# ECB01-Kit-V1_0.net
KiCad netlist of a schematic drawn in Altium Designer
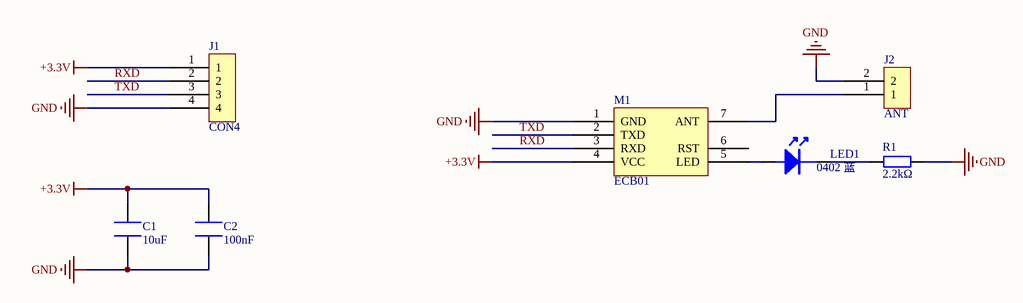
[diagram p0: ECB01-Kit-V1.0.SchDoc]

(export (version "E")
  (design (tool "Eeschema 10.0.6"))
  (components
    (comp (ref "C1") (value "10uF") (footprint "0402") (libsource (lib "ECB01-Kit-V1.0") (part "C")))
    (comp (ref "C2") (value "100nF") (footprint "0402") (libsource (lib "ECB01-Kit-V1.0") (part "C")))
    (comp (ref "J1") (value "CON4") (footprint "SIP04") (libsource (lib "ECB01-Kit-V1.0") (part "CON4")))
    (comp (ref "J2") (value "ANT") (footprint "SMA") (libsource (lib "ECB01-Kit-V1.0") (part "ANT")))
    (comp (ref "LED1")
      (value "0402 蓝")
      (footprint "0402-led")
      (libsource (lib "ECB01-Kit-V1.0") (part "LED-0402"))
    )
    (comp (ref "M1") (value "ECB01") (footprint "ECB01") (libsource (lib "ECB01-Kit-V1.0") (part "ECB01")))
    (comp (ref "R1") (value "2.2kΩ") (footprint "0402") (libsource (lib "ECB01-Kit-V1.0") (part "R")))
  )
  (nets
    (net (code "1") (name "+3.3V") (class "Default")
      (node (ref "C1") (pin "2") (pinfunction "2_2") (pintype "passive"))
      (node (ref "C2") (pin "2") (pinfunction "2_2") (pintype "passive"))
      (node (ref "J1") (pin "1") (pinfunction "1_1") (pintype "passive"))
      (node (ref "M1") (pin "4") (pinfunction "VCC_4") (pintype "passive"))
    )
    (net (code "2") (name "/RXD") (class "Default")
      (node (ref "J1") (pin "2") (pinfunction "2_2") (pintype "passive"))
      (node (ref "M1") (pin "3") (pinfunction "RXD_3") (pintype "passive"))
    )
    (net (code "3") (name "/TXD") (class "Default")
      (node (ref "J1") (pin "3") (pinfunction "3_3") (pintype "passive"))
      (node (ref "M1") (pin "2") (pinfunction "TXD_2") (pintype "passive"))
    )
    (net (code "4") (name "GND") (class "Default")
      (node (ref "C1") (pin "1") (pinfunction "1_1") (pintype "passive"))
      (node (ref "C2") (pin "1") (pinfunction "1_1") (pintype "passive"))
      (node (ref "J1") (pin "4") (pinfunction "4_4") (pintype "passive"))
      (node (ref "J2") (pin "2") (pinfunction "2_2") (pintype "passive"))
      (node (ref "M1") (pin "1") (pinfunction "GND_1") (pintype "passive"))
      (node (ref "R1") (pin "2") (pinfunction "2_2") (pintype "passive"))
    )
    (net (code "5") (name "Net-(LED1-Pad2)") (class "Default")
      (node (ref "LED1") (pin "2") (pinfunction "2_2") (pintype "passive"))
      (node (ref "R1") (pin "1") (pinfunction "1_1") (pintype "passive"))
    )
    (net (code "6") (name "Net-(M1-ANT)") (class "Default")
      (node (ref "J2") (pin "1") (pinfunction "1_1") (pintype "passive"))
      (node (ref "M1") (pin "7") (pinfunction "ANT_7") (pintype "passive"))
    )
    (net (code "7") (name "Net-(M1-LED)") (class "Default")
      (node (ref "LED1") (pin "1") (pinfunction "1_1") (pintype "passive"))
      (node (ref "M1") (pin "5") (pinfunction "LED_5") (pintype "passive"))
    )
    (net (code "8") (name "unconnected-(M1-RST-Pad6)") (class "Default")
      (node (ref "M1") (pin "6") (pinfunction "RST_6") (pintype "passive"))
    )
  )
)
